# yard-ice-cpu.net
KiCad netlist of a schematic drawn in Altium Designer
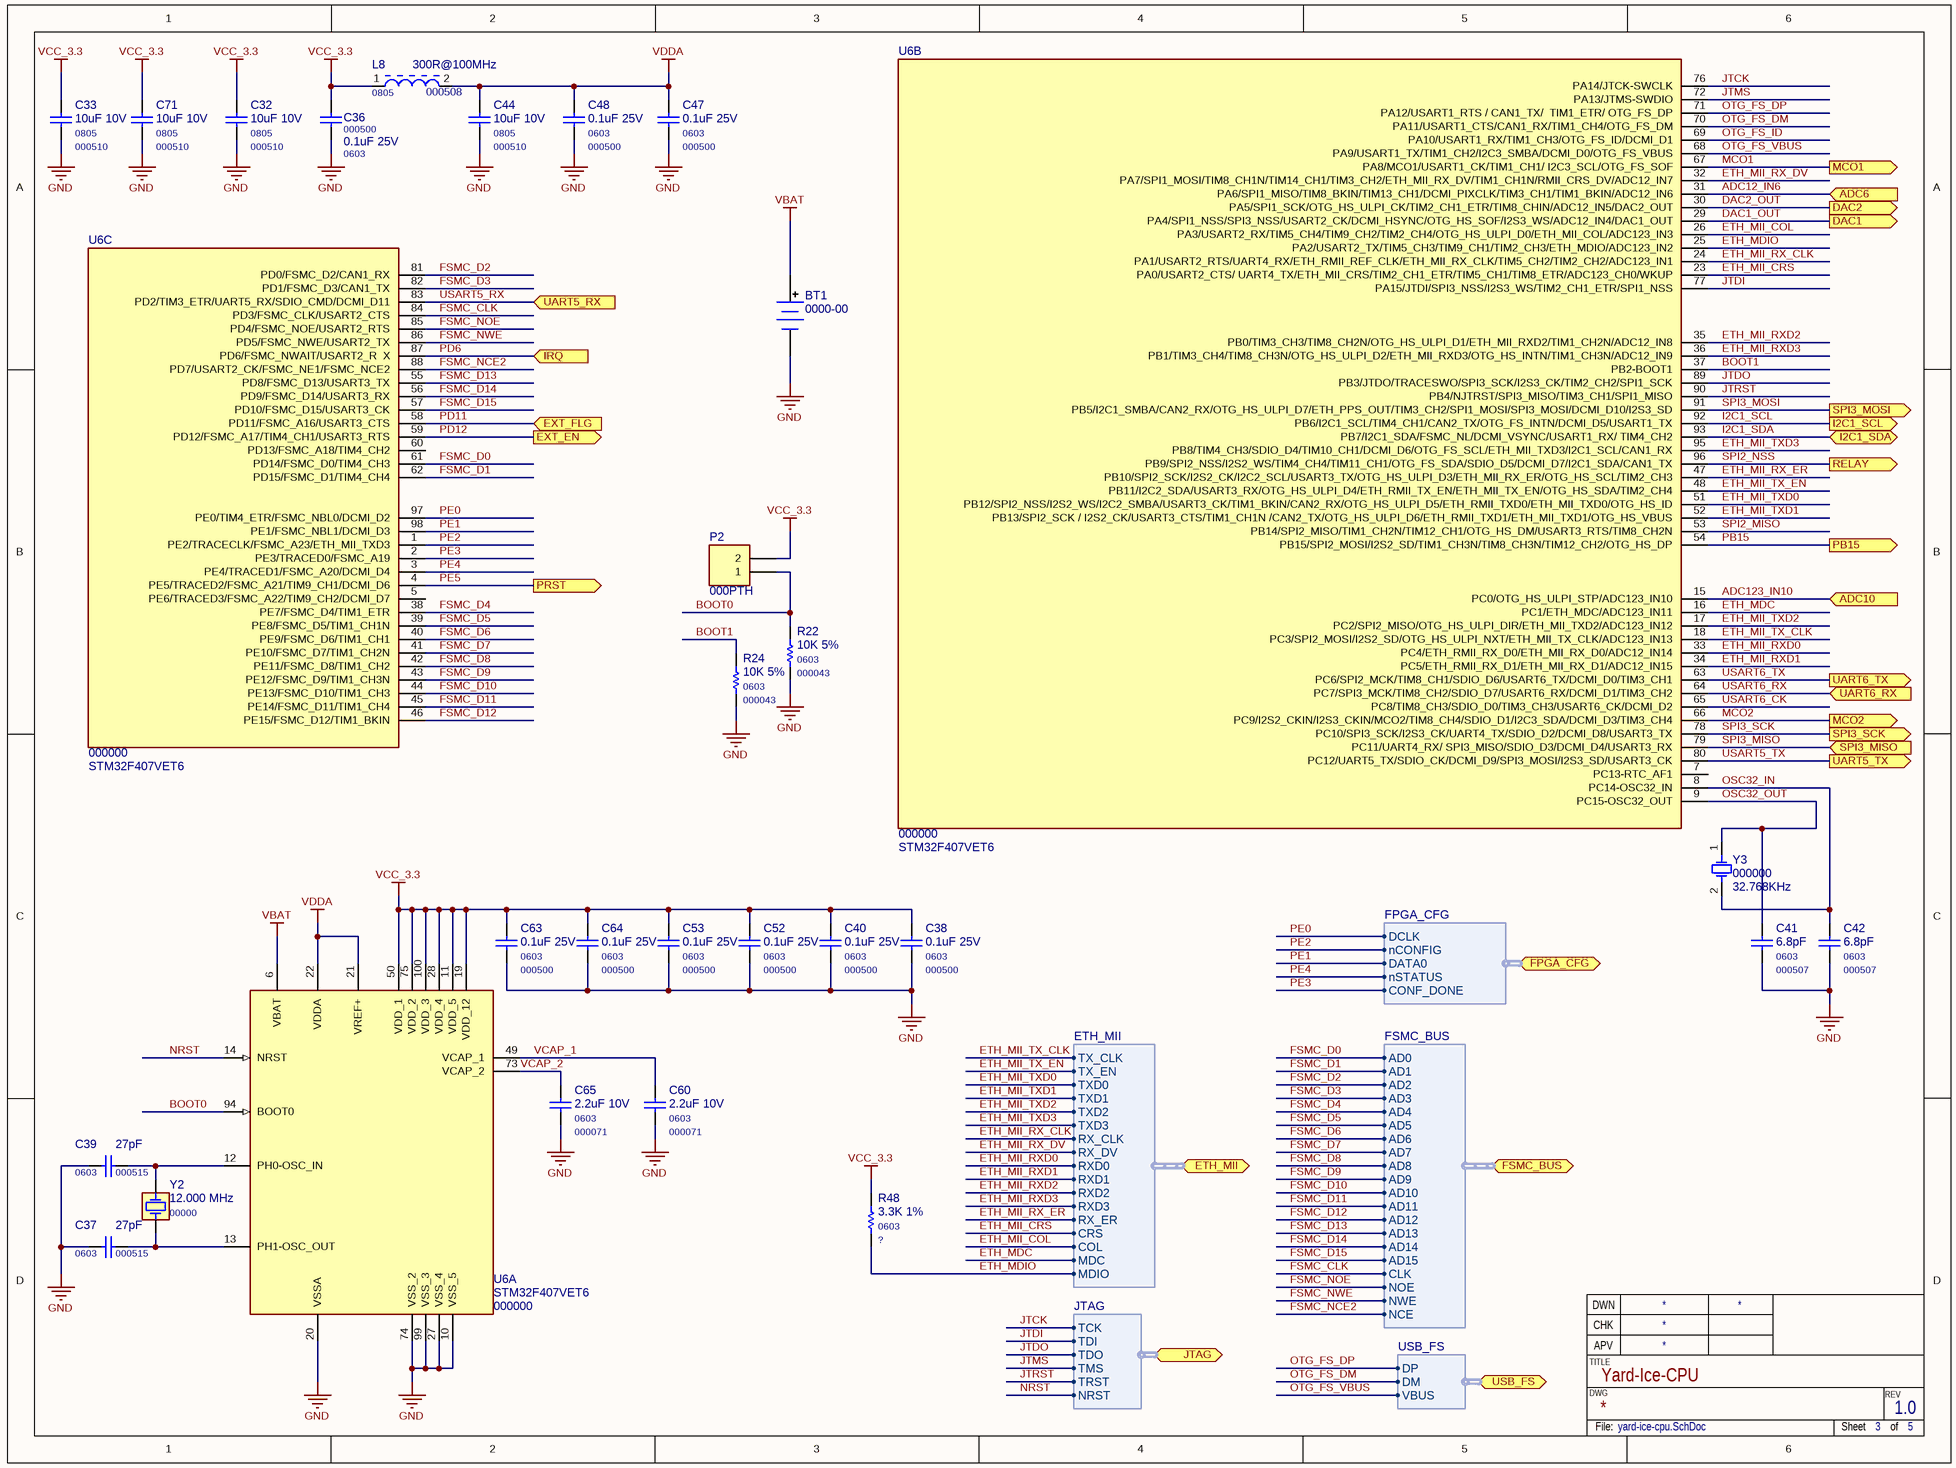
[diagram p0: yard-ice-cpu.SchDoc]

(export (version "E")
  (design (tool "Eeschema 10.0.6"))
  (components
    (comp (ref "BT1")
      (value "0000-00")
      (footprint "CR-1632/VCN")
      (description "PTH 16mm SMD Battery Vertical")
      (fields (field (name "MF") "Panasonic"))
      (libsource (lib "discrete-pth") (part "CR-1632/VCN"))
    )
    (comp (ref "C32")
      (value "TDK")
      (footprint "C0805M")
      (description "SMD Ceramic Chip Capacitor - 0805 - X7R")
      (fields (field (name "ALTIUM_VALUE") "10uF 10V") (field (name "PACKAGE") "0805"))
      (libsource (lib "discrete-sm") (part "C0805"))
    )
    (comp (ref "C33")
      (value "TDK")
      (footprint "C0805M")
      (description "SMD Ceramic Chip Capacitor - 0805 - X7R")
      (fields (field (name "ALTIUM_VALUE") "10uF 10V") (field (name "PACKAGE") "0805"))
      (libsource (lib "discrete-sm") (part "C0805"))
    )
    (comp (ref "C36")
      (value "000500")
      (footprint "C0603M")
      (description "SMD Ceramic Chip Capacitor - 0603 - X7R")
      (fields
        (field (name "ALTIUM_VALUE") "0.1uF 25V")
        (field (name "PACKAGE") "0603")
        (field (name "MF") "TDK")
      )
      (libsource (lib "discrete-sm") (part "C0603"))
    )
    (comp (ref "C37")
      (value "000515")
      (footprint "C0603M")
      (description "SMD Ceramic Chip Capacitor - 0603")
      (fields (field (name "ALTIUM_VALUE") "27pF") (field (name "PACKAGE") "0603"))
      (libsource (lib "discrete-sm") (part "C0603"))
    )
    (comp (ref "C38")
      (value "000500")
      (footprint "C0603M")
      (description "SMD Ceramic Chip Capacitor - 0603 - X7R")
      (fields
        (field (name "ALTIUM_VALUE") "0.1uF 25V")
        (field (name "PACKAGE") "0603")
        (field (name "MF") "TDK")
      )
      (libsource (lib "discrete-sm") (part "C0603"))
    )
    (comp (ref "C39")
      (value "000515")
      (footprint "C0603M")
      (description "SMD Ceramic Chip Capacitor - 0603")
      (fields (field (name "ALTIUM_VALUE") "27pF") (field (name "PACKAGE") "0603"))
      (libsource (lib "discrete-sm") (part "C0603"))
    )
    (comp (ref "C40")
      (value "000500")
      (footprint "C0603M")
      (description "SMD Ceramic Chip Capacitor - 0603 - X7R")
      (fields
        (field (name "ALTIUM_VALUE") "0.1uF 25V")
        (field (name "PACKAGE") "0603")
        (field (name "MF") "TDK")
      )
      (libsource (lib "discrete-sm") (part "C0603"))
    )
    (comp (ref "C41")
      (value "000507")
      (footprint "C0603M")
      (description "SMD Ceramic Chip Capacitor - 0603")
      (fields (field (name "ALTIUM_VALUE") "6.8pF") (field (name "PACKAGE") "0603"))
      (libsource (lib "discrete-sm") (part "C0603"))
    )
    (comp (ref "C42")
      (value "000507")
      (footprint "C0603M")
      (description "SMD Ceramic Chip Capacitor - 0603")
      (fields (field (name "ALTIUM_VALUE") "6.8pF") (field (name "PACKAGE") "0603"))
      (libsource (lib "discrete-sm") (part "C0603"))
    )
    (comp (ref "C44")
      (value "000510")
      (footprint "C0805M")
      (description "SMD Ceramic Chip Capacitor - 0805 - X7R")
      (fields
        (field (name "ALTIUM_VALUE") "10uF 10V")
        (field (name "PACKAGE") "0805")
        (field (name "MF") "TDK")
      )
      (libsource (lib "discrete-sm") (part "C0805"))
    )
    (comp (ref "C47")
      (value "000500")
      (footprint "C0603M")
      (description "SMD Ceramic Chip Capacitor - 0603 - X7R")
      (fields
        (field (name "ALTIUM_VALUE") "0.1uF 25V")
        (field (name "PACKAGE") "0603")
        (field (name "MF") "TDK")
      )
      (libsource (lib "discrete-sm") (part "C0603"))
    )
    (comp (ref "C48")
      (value "000500")
      (footprint "C0603M")
      (description "SMD Ceramic Chip Capacitor - 0603 - X7R")
      (fields
        (field (name "ALTIUM_VALUE") "0.1uF 25V")
        (field (name "PACKAGE") "0603")
        (field (name "MF") "TDK")
      )
      (libsource (lib "discrete-sm") (part "C0603"))
    )
    (comp (ref "C52")
      (value "000500")
      (footprint "C0603M")
      (description "SMD Ceramic Chip Capacitor - 0603 - X7R")
      (fields
        (field (name "ALTIUM_VALUE") "0.1uF 25V")
        (field (name "PACKAGE") "0603")
        (field (name "MF") "TDK")
      )
      (libsource (lib "discrete-sm") (part "C0603"))
    )
    (comp (ref "C53")
      (value "000500")
      (footprint "C0603M")
      (description "SMD Ceramic Chip Capacitor - 0603 - X7R")
      (fields
        (field (name "ALTIUM_VALUE") "0.1uF 25V")
        (field (name "PACKAGE") "0603")
        (field (name "MF") "TDK")
      )
      (libsource (lib "discrete-sm") (part "C0603"))
    )
    (comp (ref "C60")
      (value "000071")
      (footprint "C0603M")
      (description "SMD Ceramic Chip Capacitor - 0603 - X7R")
      (fields
        (field (name "ALTIUM_VALUE") "2.2uF 10V")
        (field (name "PACKAGE") "0603")
        (field (name "MF") "Taiyo Yuden")
      )
      (libsource (lib "discrete-sm") (part "C0603"))
    )
    (comp (ref "C63")
      (value "000500")
      (footprint "C0603M")
      (description "SMD Ceramic Chip Capacitor - 0603 - X7R")
      (fields
        (field (name "ALTIUM_VALUE") "0.1uF 25V")
        (field (name "PACKAGE") "0603")
        (field (name "MF") "TDK")
      )
      (libsource (lib "discrete-sm") (part "C0603"))
    )
    (comp (ref "C64")
      (value "000500")
      (footprint "C0603M")
      (description "SMD Ceramic Chip Capacitor - 0603 - X7R")
      (fields
        (field (name "ALTIUM_VALUE") "0.1uF 25V")
        (field (name "PACKAGE") "0603")
        (field (name "MF") "TDK")
      )
      (libsource (lib "discrete-sm") (part "C0603"))
    )
    (comp (ref "C65")
      (value "000071")
      (footprint "C0603M")
      (description "SMD Ceramic Chip Capacitor - 0603 - X7R")
      (fields
        (field (name "ALTIUM_VALUE") "2.2uF 10V")
        (field (name "PACKAGE") "0603")
        (field (name "MF") "Taiyo Yuden")
      )
      (libsource (lib "discrete-sm") (part "C0603"))
    )
    (comp (ref "C71")
      (value "TDK")
      (footprint "C0805M")
      (description "SMD Ceramic Chip Capacitor - 0805 - X7R")
      (fields (field (name "ALTIUM_VALUE") "10uF 10V") (field (name "PACKAGE") "0805"))
      (libsource (lib "discrete-sm") (part "C0805"))
    )
    (comp (ref "L8")
      (value "000508")
      (footprint "L0805M")
      (description "SMD Ferrite Bead 0805")
      (fields
        (field (name "ALTIUM_VALUE") "300R@100MHz")
        (field (name "PACKAGE") "0805")
        (field (name "MF") "TDK")
      )
      (libsource (lib "discrete-sm") (part "L0805"))
    )
    (comp (ref "P2")
      (value "000PTH")
      (footprint "TSW-102-07-G-S")
      (description "Header, 2-Pin")
      (libsource (lib "samtec-board-to-board") (part "Header 2"))
    )
    (comp (ref "R22")
      (value "000043")
      (footprint "R0603M")
      (description "SMD Chip Resistor - 0603")
      (fields (field (name "ALTIUM_VALUE") "10K 5%") (field (name "PACKAGE") "0603"))
      (libsource (lib "discrete-sm") (part "R0603"))
    )
    (comp (ref "R24")
      (value "000043")
      (footprint "R0603M")
      (description "SMD Chip Resistor - 0603")
      (fields (field (name "ALTIUM_VALUE") "10K 5%") (field (name "PACKAGE") "0603"))
      (libsource (lib "discrete-sm") (part "R0603"))
    )
    (comp (ref "R48")
      (value "?")
      (footprint "R0603M")
      (description "SMD Chip Resistor - 0603")
      (fields (field (name "ALTIUM_VALUE") "3.3K 1%") (field (name "PACKAGE") "0603"))
      (libsource (lib "discrete-sm") (part "R0603"))
    )
    (comp (ref "U6")
      (value "000000")
      (footprint "LQFP100")
      (fields (field (name "ALTIUM_VALUE") "STM32F407VET6"))
      (libsource (lib "st") (part "STM32F407VET6"))
    )
    (comp (ref "Y2")
      (value "00000")
      (footprint "ABM3-H")
      (description "Miniature Ceramic SMD Crystal")
      (fields (field (name "MF") "Abracon") (field (name "ALTIUM_VALUE") "12.000 MHz"))
      (libsource (lib "abracon") (part "ABM3"))
    )
    (comp (ref "Y3")
      (value "000000")
      (footprint "CA-301-V")
      (description "Cylinder Crystal Unit")
      (fields (field (name "MF") "Epson") (field (name "ALTIUM_VALUE") "32.768KHz"))
      (libsource (lib "epson-xtal") (part "CA-301"))
    )
  )
  (nets
    (net (code "6") (name "/ADC12_IN6") (class "Default")
      (node (ref "U6") (pin "31") (pinfunction "PA6/SPI1_MISO/TIM8_BKIN/TIM13_CH1/DCMI_PIXCLK/TIM3_CH1/TIM1_BKIN/ADC12_IN6_31") (pintype "tri_state"))
    )
    (net (code "7") (name "/ADC123_IN10") (class "Default")
      (node (ref "U6") (pin "15") (pinfunction "PC0/OTG_HS_ULPI_STP/ADC123_IN10_15") (pintype "tri_state"))
    )
    (net (code "8") (name "/BOOT0") (class "Default")
      (node (ref "P2") (pin "1") (pinfunction "1_1") (pintype "passive"))
      (node (ref "R22") (pin "2") (pinfunction "2_2") (pintype "passive"))
      (node (ref "U6") (pin "94") (pinfunction "BOOT0_94") (pintype "input"))
    )
    (net (code "9") (name "/BOOT1") (class "Default")
      (node (ref "R24") (pin "2") (pinfunction "2_2") (pintype "passive"))
      (node (ref "U6") (pin "37") (pinfunction "PB2-BOOT1_37") (pintype "tri_state"))
    )
    (net (code "10") (name "/DAC1_OUT") (class "Default")
      (node (ref "U6") (pin "29") (pinfunction "PA4/SPI1_NSS/SPI3_NSS/USART2_CK/DCMI_HSYNC/OTG_HS_SOF/I2S3_WS/ADC12_IN4/DAC1_OUT_29") (pintype "tri_state"))
    )
    (net (code "11") (name "/DAC2_OUT") (class "Default")
      (node (ref "U6") (pin "30") (pinfunction "PA5/SPI1_SCK/OTG_HS_ULPI_CK/TIM2_CH1_ETR/TIM8_CHIN/ADC12_IN5/DAC2_OUT_30") (pintype "tri_state"))
    )
    (net (code "12") (name "/ETH_MDC") (class "Default")
      (node (ref "U6") (pin "16") (pinfunction "PC1/ETH_MDC/ADC123_IN11_16") (pintype "tri_state"))
    )
    (net (code "13") (name "/ETH_MDIO") (class "Default")
      (node (ref "R48") (pin "1") (pinfunction "1_1") (pintype "passive"))
      (node (ref "U6") (pin "25") (pinfunction "PA2/USART2_TX/TIM5_CH3/TIM9_CH1/TIM2_CH3/ETH_MDIO/ADC123_IN2_25") (pintype "tri_state"))
    )
    (net (code "14") (name "/ETH_MII_COL") (class "Default")
      (node (ref "U6") (pin "26") (pinfunction "PA3/USART2_RX/TIM5_CH4/TIM9_CH2/TIM2_CH4/OTG_HS_ULPI_D0/ETH_MII_COL/ADC123_IN3_26") (pintype "tri_state"))
    )
    (net (code "15") (name "/ETH_MII_CRS") (class "Default")
      (node (ref "U6") (pin "23") (pinfunction "PA0/USART2_CTS/_UART4_TX/ETH_MII_CRS/TIM2_CH1_ETR/TIM5_CH1/TIM8_ETR/ADC123_CH0/WKUP_23") (pintype "tri_state"))
    )
    (net (code "16") (name "/ETH_MII_RXD0") (class "Default")
      (node (ref "U6") (pin "33") (pinfunction "PC4/ETH_RMII_RX_D0/ETH_MII_RX_D0/ADC12_IN14_33") (pintype "tri_state"))
    )
    (net (code "17") (name "/ETH_MII_RXD1") (class "Default")
      (node (ref "U6") (pin "34") (pinfunction "PC5/ETH_RMII_RX_D1/ETH_MII_RX_D1/ADC12_IN15_34") (pintype "tri_state"))
    )
    (net (code "18") (name "/ETH_MII_RXD2") (class "Default")
      (node (ref "U6") (pin "35") (pinfunction "PB0/TIM3_CH3/TIM8_CH2N/OTG_HS_ULPI_D1/ETH_MII_RXD2/TIM1_CH2N/ADC12_IN8_35") (pintype "tri_state"))
    )
    (net (code "19") (name "/ETH_MII_RXD3") (class "Default")
      (node (ref "U6") (pin "36") (pinfunction "PB1/TIM3_CH4/TIM8_CH3N/OTG_HS_ULPI_D2/ETH_MII_RXD3/OTG_HS_INTN/TIM1_CH3N/ADC12_IN9_36") (pintype "tri_state"))
    )
    (net (code "20") (name "/ETH_MII_RX_CLK") (class "Default")
      (node (ref "U6") (pin "24") (pinfunction "PA1/USART2_RTS/UART4_RX/ETH_RMII_REF_CLK/ETH_MII_RX_CLK/TIM5_CH2/TIM2_CH2/ADC123_IN1_24") (pintype "tri_state"))
    )
    (net (code "21") (name "/ETH_MII_RX_DV") (class "Default")
      (node (ref "U6") (pin "32") (pinfunction "PA7/SPI1_MOSI/TIM8_CH1N/TIM14_CH1/TIM3_CH2/ETH_MII_RX_DV/TIM1_CH1N/RMII_CRS_DV/ADC12_IN7_32") (pintype "tri_state"))
    )
    (net (code "22") (name "/ETH_MII_RX_ER") (class "Default")
      (node (ref "U6") (pin "47") (pinfunction "PB10/SPI2_SCK/I2S2_CK/I2C2_SCL/USART3_TX/OTG_HS_ULPI_D3/ETH_MII_RX_ER/OTG_HS_SCL/TIM2_CH3_47") (pintype "tri_state"))
    )
    (net (code "23") (name "/ETH_MII_TXD0") (class "Default")
      (node (ref "U6") (pin "51") (pinfunction "PB12/SPI2_NSS/I2S2_WS/I2C2_SMBA/USART3_CK/TIM1_BKIN/CAN2_RX/OTG_HS_ULPI_D5/ETH_RMII_TXD0/ETH_MII_TXD0/OTG_HS_ID_51") (pintype "tri_state"))
    )
    (net (code "24") (name "/ETH_MII_TXD1") (class "Default")
      (node (ref "U6") (pin "52") (pinfunction "PB13/SPI2_SCK_/_I2S2_CK/USART3_CTS/TIM1_CH1N_/CAN2_TX/OTG_HS_ULPI_D6/ETH_RMII_TXD1/ETH_MII_TXD1/OTG_HS_VBUS_52") (pintype "tri_state"))
    )
    (net (code "25") (name "/ETH_MII_TXD2") (class "Default")
      (node (ref "U6") (pin "17") (pinfunction "PC2/SPI2_MISO/OTG_HS_ULPI_DIR/ETH_MII_TXD2/ADC123_IN12_17") (pintype "tri_state"))
    )
    (net (code "26") (name "/ETH_MII_TXD3") (class "Default")
      (node (ref "U6") (pin "95") (pinfunction "PB8/TIM4_CH3/SDIO_D4/TIM10_CH1/DCMI_D6/OTG_FS_SCL/ETH_MII_TXD3/I2C1_SCL/CAN1_RX_95") (pintype "tri_state"))
    )
    (net (code "27") (name "/ETH_MII_TX_CLK") (class "Default")
      (node (ref "U6") (pin "18") (pinfunction "PC3/SPI2_MOSI/I2S2_SD/OTG_HS_ULPI_NXT/ETH_MII_TX_CLK/ADC123_IN13_18") (pintype "tri_state"))
    )
    (net (code "28") (name "/ETH_MII_TX_EN") (class "Default")
      (node (ref "U6") (pin "48") (pinfunction "PB11/I2C2_SDA/USART3_RX/OTG_HS_ULPI_D4/ETH_RMII_TX_EN/ETH_MII_TX_EN/OTG_HS_SDA/TIM2_CH4_48") (pintype "tri_state"))
    )
    (net (code "29") (name "/FSMC_CLK") (class "Default")
      (node (ref "U6") (pin "84") (pinfunction "PD3/FSMC_CLK/USART2_CTS_84") (pintype "tri_state"))
    )
    (net (code "30") (name "/FSMC_D0") (class "Default")
      (node (ref "U6") (pin "61") (pinfunction "PD14/FSMC_D0/TIM4_CH3_61") (pintype "tri_state"))
    )
    (net (code "31") (name "/FSMC_D1") (class "Default")
      (node (ref "U6") (pin "62") (pinfunction "PD15/FSMC_D1/TIM4_CH4_62") (pintype "tri_state"))
    )
    (net (code "32") (name "/FSMC_D2") (class "Default")
      (node (ref "U6") (pin "81") (pinfunction "PD0/FSMC_D2/CAN1_RX_81") (pintype "tri_state"))
    )
    (net (code "33") (name "/FSMC_D3") (class "Default")
      (node (ref "U6") (pin "82") (pinfunction "PD1/FSMC_D3/CAN1_TX_82") (pintype "tri_state"))
    )
    (net (code "34") (name "/FSMC_D4") (class "Default")
      (node (ref "U6") (pin "38") (pinfunction "PE7/FSMC_D4/TIM1_ETR_38") (pintype "tri_state"))
    )
    (net (code "35") (name "/FSMC_D5") (class "Default")
      (node (ref "U6") (pin "39") (pinfunction "PE8/FSMC_D5/TIM1_CH1N_39") (pintype "tri_state"))
    )
    (net (code "36") (name "/FSMC_D6") (class "Default")
      (node (ref "U6") (pin "40") (pinfunction "PE9/FSMC_D6/TIM1_CH1_40") (pintype "tri_state"))
    )
    (net (code "37") (name "/FSMC_D7") (class "Default")
      (node (ref "U6") (pin "41") (pinfunction "PE10/FSMC_D7/TIM1_CH2N_41") (pintype "tri_state"))
    )
    (net (code "38") (name "/FSMC_D8") (class "Default")
      (node (ref "U6") (pin "42") (pinfunction "PE11/FSMC_D8/TIM1_CH2_42") (pintype "tri_state"))
    )
    (net (code "39") (name "/FSMC_D9") (class "Default")
      (node (ref "U6") (pin "43") (pinfunction "PE12/FSMC_D9/TIM1_CH3N_43") (pintype "tri_state"))
    )
    (net (code "40") (name "/FSMC_D10") (class "Default")
      (node (ref "U6") (pin "44") (pinfunction "PE13/FSMC_D10/TIM1_CH3_44") (pintype "tri_state"))
    )
    (net (code "41") (name "/FSMC_D11") (class "Default")
      (node (ref "U6") (pin "45") (pinfunction "PE14/FSMC_D11/TIM1_CH4_45") (pintype "tri_state"))
    )
    (net (code "42") (name "/FSMC_D12") (class "Default")
      (node (ref "U6") (pin "46") (pinfunction "PE15/FSMC_D12/TIM1_BKIN_46") (pintype "tri_state"))
    )
    (net (code "43") (name "/FSMC_D13") (class "Default")
      (node (ref "U6") (pin "55") (pinfunction "PD8/FSMC_D13/USART3_TX_55") (pintype "tri_state"))
    )
    (net (code "44") (name "/FSMC_D14") (class "Default")
      (node (ref "U6") (pin "56") (pinfunction "PD9/FSMC_D14/USART3_RX_56") (pintype "tri_state"))
    )
    (net (code "45") (name "/FSMC_D15") (class "Default")
      (node (ref "U6") (pin "57") (pinfunction "PD10/FSMC_D15/USART3_CK_57") (pintype "tri_state"))
    )
    (net (code "46") (name "/FSMC_NCE2") (class "Default")
      (node (ref "U6") (pin "88") (pinfunction "PD7/USART2_CK/FSMC_NE1/FSMC_NCE2_88") (pintype "tri_state"))
    )
    (net (code "47") (name "/FSMC_NOE") (class "Default")
      (node (ref "U6") (pin "85") (pinfunction "PD4/FSMC_NOE/USART2_RTS_85") (pintype "tri_state"))
    )
    (net (code "48") (name "/FSMC_NWE") (class "Default")
      (node (ref "U6") (pin "86") (pinfunction "PD5/FSMC_NWE/USART2_TX_86") (pintype "tri_state"))
    )
    (net (code "49") (name "/I2C1_SCL") (class "Default")
      (node (ref "U6") (pin "92") (pinfunction "PB6/I2C1_SCL/TIM4_CH1/CAN2_TX/OTG_FS_INTN/DCMI_D5/USART1_TX_92") (pintype "tri_state"))
    )
    (net (code "50") (name "/I2C1_SDA") (class "Default")
      (node (ref "U6") (pin "93") (pinfunction "PB7/I2C1_SDA/FSMC_NL/DCMI_VSYNC/USART1_RX/_TIM4_CH2_93") (pintype "tri_state"))
    )
    (net (code "51") (name "/JTCK") (class "Default")
      (node (ref "U6") (pin "76") (pinfunction "PA14/JTCK-SWCLK_76") (pintype "tri_state"))
    )
    (net (code "52") (name "/JTDI") (class "Default")
      (node (ref "U6") (pin "77") (pinfunction "PA15/JTDI/SPI3_NSS/I2S3_WS/TIM2_CH1_ETR/SPI1_NSS_77") (pintype "tri_state"))
    )
    (net (code "53") (name "/JTDO") (class "Default")
      (node (ref "U6") (pin "89") (pinfunction "PB3/JTDO/TRACESWO/SPI3_SCK/I2S3_CK/TIM2_CH2/SPI1_SCK_89") (pintype "tri_state"))
    )
    (net (code "54") (name "/JTMS") (class "Default")
      (node (ref "U6") (pin "72") (pinfunction "PA13/JTMS-SWDIO_72") (pintype "tri_state"))
    )
    (net (code "55") (name "/JTRST") (class "Default")
      (node (ref "U6") (pin "90") (pinfunction "PB4/NJTRST/SPI3_MISO/TIM3_CH1/SPI1_MISO_90") (pintype "tri_state"))
    )
    (net (code "56") (name "/MCO1") (class "Default")
      (node (ref "U6") (pin "67") (pinfunction "PA8/MCO1/USART1_CK/TIM1_CH1/_I2C3_SCL/OTG_FS_SOF_67") (pintype "tri_state"))
    )
    (net (code "57") (name "/MCO2") (class "Default")
      (node (ref "U6") (pin "66") (pinfunction "PC9/I2S2_CKIN/I2S3_CKIN/MCO2/TIM8_CH4/SDIO_D1/I2C3_SDA/DCMI_D3/TIM3_CH4_66") (pintype "tri_state"))
    )
    (net (code "58") (name "/NRST") (class "Default")
      (node (ref "U6") (pin "14") (pinfunction "NRST_14") (pintype "input"))
    )
    (net (code "59") (name "/OSC32_IN") (class "Default")
      (node (ref "C42") (pin "2") (pinfunction "2_2") (pintype "passive"))
      (node (ref "U6") (pin "8") (pinfunction "PC14-OSC32_IN_8") (pintype "tri_state"))
      (node (ref "Y3") (pin "2") (pinfunction "2_2") (pintype "passive"))
    )
    (net (code "60") (name "/OSC32_OUT") (class "Default")
      (node (ref "C41") (pin "2") (pinfunction "2_2") (pintype "passive"))
      (node (ref "U6") (pin "9") (pinfunction "PC15-OSC32_OUT_9") (pintype "tri_state"))
      (node (ref "Y3") (pin "1") (pinfunction "1_1") (pintype "passive"))
    )
    (net (code "61") (name "/OTG_FS_DM") (class "Default")
      (node (ref "U6") (pin "70") (pinfunction "PA11/USART1_CTS/CAN1_RX/TIM1_CH4/OTG_FS_DM_70") (pintype "tri_state"))
    )
    (net (code "62") (name "/OTG_FS_DP") (class "Default")
      (node (ref "U6") (pin "71") (pinfunction "PA12/USART1_RTS_/_CAN1_TX/__TIM1_ETR/_OTG_FS_DP_71") (pintype "tri_state"))
    )
    (net (code "63") (name "/OTG_FS_ID") (class "Default")
      (node (ref "U6") (pin "69") (pinfunction "PA10/USART1_RX/TIM1_CH3/OTG_FS_ID/DCMI_D1_69") (pintype "tri_state"))
    )
    (net (code "64") (name "/OTG_FS_VBUS") (class "Default")
      (node (ref "U6") (pin "68") (pinfunction "PA9/USART1_TX/TIM1_CH2/I2C3_SMBA/DCMI_D0/OTG_FS_VBUS_68") (pintype "tri_state"))
    )
    (net (code "65") (name "/PB15") (class "Default")
      (node (ref "U6") (pin "54") (pinfunction "PB15/SPI2_MOSI/I2S2_SD/TIM1_CH3N/TIM8_CH3N/TIM12_CH2/OTG_HS_DP_54") (pintype "tri_state"))
    )
    (net (code "66") (name "/PD6") (class "Default")
      (node (ref "U6") (pin "87") (pinfunction "PD6/FSMC_NWAIT/USART2_R__X_87") (pintype "tri_state"))
    )
    (net (code "67") (name "/PD11") (class "Default")
      (node (ref "U6") (pin "58") (pinfunction "PD11/FSMC_A16/USART3_CTS_58") (pintype "tri_state"))
    )
    (net (code "68") (name "/PD12") (class "Default")
      (node (ref "U6") (pin "59") (pinfunction "PD12/FSMC_A17/TIM4_CH1/USART3_RTS_59") (pintype "tri_state"))
    )
    (net (code "69") (name "/PE0") (class "Default")
      (node (ref "U6") (pin "97") (pinfunction "PE0/TIM4_ETR/FSMC_NBL0/DCMI_D2_97") (pintype "tri_state"))
    )
    (net (code "70") (name "/PE1") (class "Default")
      (node (ref "U6") (pin "98") (pinfunction "PE1/FSMC_NBL1/DCMI_D3_98") (pintype "tri_state"))
    )
    (net (code "71") (name "/PE2") (class "Default")
      (node (ref "U6") (pin "1") (pinfunction "PE2/TRACECLK/FSMC_A23/ETH_MII_TXD3_1") (pintype "tri_state"))
    )
    (net (code "72") (name "/PE3") (class "Default")
      (node (ref "U6") (pin "2") (pinfunction "PE3/TRACED0/FSMC_A19_2") (pintype "tri_state"))
    )
    (net (code "73") (name "/PE4") (class "Default")
      (node (ref "U6") (pin "3") (pinfunction "PE4/TRACED1/FSMC_A20/DCMI_D4_3") (pintype "tri_state"))
    )
    (net (code "74") (name "/PE5") (class "Default")
      (node (ref "U6") (pin "4") (pinfunction "PE5/TRACED2/FSMC_A21/TIM9_CH1/DCMI_D6_4") (pintype "tri_state"))
    )
    (net (code "75") (name "/SPI2_MISO") (class "Default")
      (node (ref "U6") (pin "53") (pinfunction "PB14/SPI2_MISO/TIM1_CH2N/TIM12_CH1/OTG_HS_DM/USART3_RTS/TIM8_CH2N_53") (pintype "tri_state"))
    )
    (net (code "76") (name "/SPI2_NSS") (class "Default")
      (node (ref "U6") (pin "96") (pinfunction "PB9/SPI2_NSS/I2S2_WS/TIM4_CH4/TIM11_CH1/OTG_FS_SDA/SDIO_D5/DCMI_D7/I2C1_SDA/CAN1_TX_96") (pintype "tri_state"))
    )
    (net (code "77") (name "/SPI3_MISO") (class "Default")
      (node (ref "U6") (pin "79") (pinfunction "PC11/UART4_RX/_SPI3_MISO/SDIO_D3/DCMI_D4/USART3_RX_79") (pintype "tri_state"))
    )
    (net (code "78") (name "/SPI3_MOSI") (class "Default")
      (node (ref "U6") (pin "91") (pinfunction "PB5/I2C1_SMBA/CAN2_RX/OTG_HS_ULPI_D7/ETH_PPS_OUT/TIM3_CH2/SPI1_MOSI/SPI3_MOSI/DCMI_D10/I2S3_SD_91") (pintype "tri_state"))
    )
    (net (code "79") (name "/SPI3_SCK") (class "Default")
      (node (ref "U6") (pin "78") (pinfunction "PC10/SPI3_SCK/I2S3_CK/UART4_TX/SDIO_D2/DCMI_D8/USART3_TX_78") (pintype "tri_state"))
    )
    (net (code "80") (name "/USART5_RX") (class "Default")
      (node (ref "U6") (pin "83") (pinfunction "PD2/TIM3_ETR/UART5_RX/SDIO_CMD/DCMI_D11_83") (pintype "tri_state"))
    )
    (net (code "81") (name "/USART5_TX") (class "Default")
      (node (ref "U6") (pin "80") (pinfunction "PC12/UART5_TX/SDIO_CK/DCMI_D9/SPI3_MOSI/I2S3_SD/USART3_CK_80") (pintype "tri_state"))
    )
    (net (code "82") (name "/USART6_CK") (class "Default")
      (node (ref "U6") (pin "65") (pinfunction "PC8/TIM8_CH3/SDIO_D0/TIM3_CH3/USART6_CK/DCMI_D2_65") (pintype "tri_state"))
    )
    (net (code "83") (name "/USART6_RX") (class "Default")
      (node (ref "U6") (pin "64") (pinfunction "PC7/SPI3_MCK/TIM8_CH2/SDIO_D7/USART6_RX/DCMI_D1/TIM3_CH2_64") (pintype "tri_state"))
    )
    (net (code "84") (name "/USART6_TX") (class "Default")
      (node (ref "U6") (pin "63") (pinfunction "PC6/SPI2_MCK/TIM8_CH1/SDIO_D6/USART6_TX/DCMI_D0/TIM3_CH1_63") (pintype "tri_state"))
    )
    (net (code "85") (name "/VCAP_1") (class "Default")
      (node (ref "C60") (pin "1") (pinfunction "1_1") (pintype "passive"))
      (node (ref "U6") (pin "49") (pinfunction "VCAP_1_49") (pintype "power_in"))
    )
    (net (code "86") (name "/VCAP_2") (class "Default")
      (node (ref "C65") (pin "1") (pinfunction "1_1") (pintype "passive"))
      (node (ref "U6") (pin "73") (pinfunction "VCAP_2_73") (pintype "power_in"))
    )
    (net (code "92") (name "GND") (class "Default")
      (node (ref "BT1") (pin "2") (pinfunction "-_2") (pintype "passive"))
      (node (ref "C32") (pin "2") (pinfunction "2_2") (pintype "passive"))
      (node (ref "C33") (pin "2") (pinfunction "2_2") (pintype "passive"))
      (node (ref "C36") (pin "2") (pinfunction "2_2") (pintype "passive"))
      (node (ref "C37") (pin "1") (pinfunction "1_1") (pintype "passive"))
      (node (ref "C38") (pin "2") (pinfunction "2_2") (pintype "passive"))
      (node (ref "C39") (pin "1") (pinfunction "1_1") (pintype "passive"))
      (node (ref "C40") (pin "2") (pinfunction "2_2") (pintype "passive"))
      (node (ref "C41") (pin "1") (pinfunction "1_1") (pintype "passive"))
      (node (ref "C42") (pin "1") (pinfunction "1_1") (pintype "passive"))
      (node (ref "C44") (pin "2") (pinfunction "2_2") (pintype "passive"))
      (node (ref "C47") (pin "2") (pinfunction "2_2") (pintype "passive"))
      (node (ref "C48") (pin "2") (pinfunction "2_2") (pintype "passive"))
      (node (ref "C52") (pin "2") (pinfunction "2_2") (pintype "passive"))
      (node (ref "C53") (pin "2") (pinfunction "2_2") (pintype "passive"))
      (node (ref "C60") (pin "2") (pinfunction "2_2") (pintype "passive"))
      (node (ref "C63") (pin "2") (pinfunction "2_2") (pintype "passive"))
      (node (ref "C64") (pin "2") (pinfunction "2_2") (pintype "passive"))
      (node (ref "C65") (pin "2") (pinfunction "2_2") (pintype "passive"))
      (node (ref "C71") (pin "2") (pinfunction "2_2") (pintype "passive"))
      (node (ref "R22") (pin "1") (pinfunction "1_1") (pintype "passive"))
      (node (ref "R24") (pin "1") (pinfunction "1_1") (pintype "passive"))
      (node (ref "U6") (pin "10") (pinfunction "VSS_5_10") (pintype "power_in"))
      (node (ref "U6") (pin "20") (pinfunction "VSSA_20") (pintype "power_in"))
      (node (ref "U6") (pin "27") (pinfunction "VSS_4_27") (pintype "power_in"))
      (node (ref "U6") (pin "74") (pinfunction "VSS_2_74") (pintype "power_in"))
      (node (ref "U6") (pin "99") (pinfunction "VSS_3_99") (pintype "passive"))
    )
    (net (code "93") (name "Net-(U6A-PH0-OSC_IN)") (class "Default")
      (node (ref "C39") (pin "2") (pinfunction "2_2") (pintype "passive"))
      (node (ref "U6") (pin "12") (pinfunction "PH0-OSC_IN_12") (pintype "tri_state"))
      (node (ref "Y2") (pin "1") (pinfunction "1_1") (pintype "passive"))
    )
    (net (code "94") (name "Net-(U6A-PH1-OSC_OUT)") (class "Default")
      (node (ref "C37") (pin "2") (pinfunction "2_2") (pintype "passive"))
      (node (ref "U6") (pin "13") (pinfunction "PH1-OSC_OUT_13") (pintype "tri_state"))
      (node (ref "Y2") (pin "2") (pinfunction "2_2") (pintype "passive"))
    )
    (net (code "95") (name "VBAT") (class "Default")
      (node (ref "BT1") (pin "1") (pinfunction "+_1") (pintype "passive"))
      (node (ref "U6") (pin "6") (pinfunction "VBAT_6") (pintype "power_in"))
    )
    (net (code "96") (name "VCC_3.3") (class "Default")
      (node (ref "C32") (pin "1") (pinfunction "1_1") (pintype "passive"))
      (node (ref "C33") (pin "1") (pinfunction "1_1") (pintype "passive"))
      (node (ref "C36") (pin "1") (pinfunction "1_1") (pintype "passive"))
      (node (ref "C38") (pin "1") (pinfunction "1_1") (pintype "passive"))
      (node (ref "C40") (pin "1") (pinfunction "1_1") (pintype "passive"))
      (node (ref "C52") (pin "1") (pinfunction "1_1") (pintype "passive"))
      (node (ref "C53") (pin "1") (pinfunction "1_1") (pintype "passive"))
      (node (ref "C63") (pin "1") (pinfunction "1_1") (pintype "passive"))
      (node (ref "C64") (pin "1") (pinfunction "1_1") (pintype "passive"))
      (node (ref "C71") (pin "1") (pinfunction "1_1") (pintype "passive"))
      (node (ref "L8") (pin "1") (pinfunction "1_1") (pintype "passive"))
      (node (ref "P2") (pin "2") (pinfunction "2_2") (pintype "passive"))
      (node (ref "R48") (pin "2") (pinfunction "2_2") (pintype "passive"))
      (node (ref "U6") (pin "100") (pinfunction "VDD_3_100") (pintype "power_in"))
      (node (ref "U6") (pin "11") (pinfunction "VDD_5_11") (pintype "power_in"))
      (node (ref "U6") (pin "19") (pinfunction "VDD_12_19") (pintype "power_in"))
      (node (ref "U6") (pin "28") (pinfunction "VDD_4_28") (pintype "power_in"))
      (node (ref "U6") (pin "50") (pinfunction "VDD_1_50") (pintype "power_in"))
      (node (ref "U6") (pin "75") (pinfunction "VDD_2_75") (pintype "power_in"))
    )
    (net (code "97") (name "VDDA") (class "Default")
      (node (ref "C44") (pin "1") (pinfunction "1_1") (pintype "passive"))
      (node (ref "C47") (pin "1") (pinfunction "1_1") (pintype "passive"))
      (node (ref "C48") (pin "1") (pinfunction "1_1") (pintype "passive"))
      (node (ref "L8") (pin "2") (pinfunction "2_2") (pintype "passive"))
      (node (ref "U6") (pin "21") (pinfunction "VREF+_21") (pintype "power_in"))
      (node (ref "U6") (pin "22") (pinfunction "VDDA_22") (pintype "power_in"))
    )
    (net (code "98") (name "unconnected-(U6B-PC13-RTC_AF1-Pad7)") (class "Default")
      (node (ref "U6") (pin "7") (pinfunction "PC13-RTC_AF1_7") (pintype "tri_state"))
    )
    (net (code "99") (name "unconnected-(U6C-PD13{slash}FSMC_A18{slash}TIM4_CH2-Pad60)") (class "Default")
      (node (ref "U6") (pin "60") (pinfunction "PD13/FSMC_A18/TIM4_CH2_60") (pintype "tri_state"))
    )
    (net (code "100") (name "unconnected-(U6C-PE6{slash}TRACED3{slash}FSMC_A22{slash}TIM9_CH2{slash}DCMI_D7-Pad5)") (class "Default")
      (node (ref "U6") (pin "5") (pinfunction "PE6/TRACED3/FSMC_A22/TIM9_CH2/DCMI_D7_5") (pintype "tri_state"))
    )
  )
)
